# 2d_printer.net
KiCad netlist of a schematic drawn in EAGLE
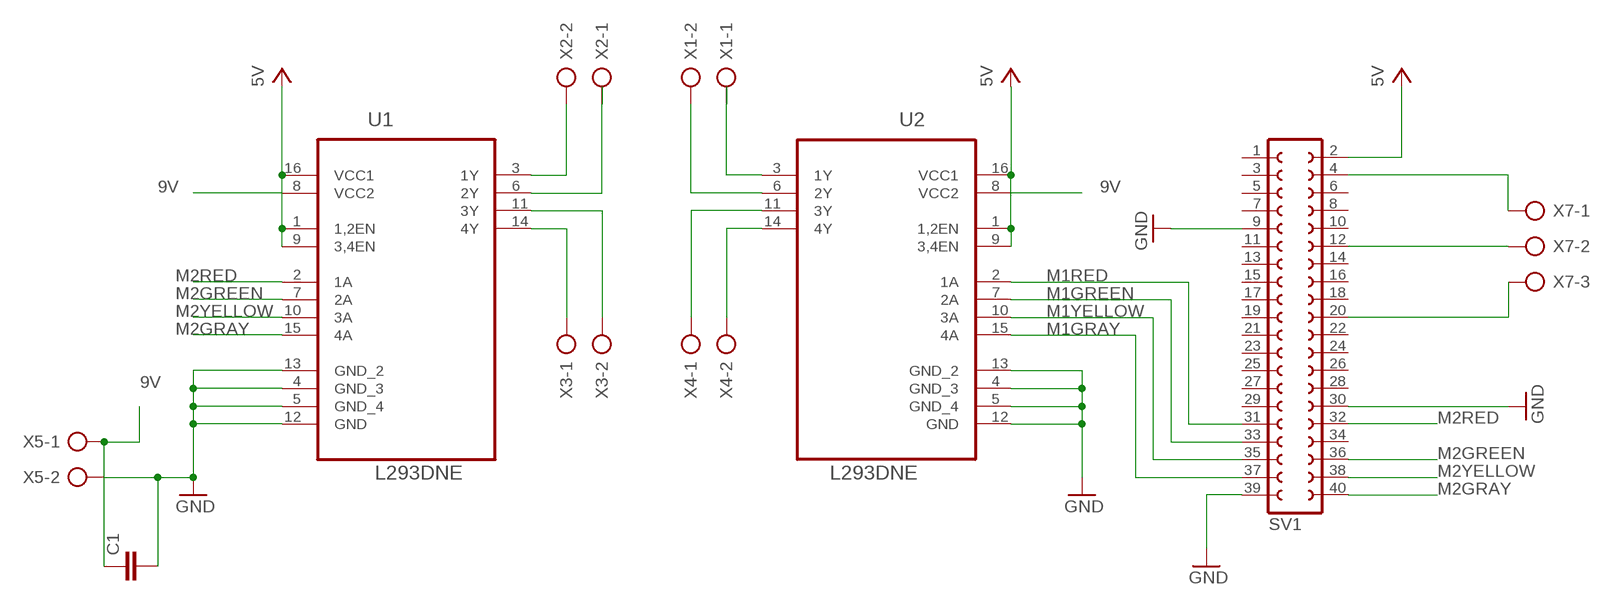
[diagram p0: schematic, sheet 1]

(export (version "E")
  (design (tool "Eeschema 10.0.6"))
  (components
    (comp (ref "C1")
      (value "C2.5/2")
      (footprint "eagle-import:C2.5-2")
      (libsource (lib "eagle-import") (part "C2.5/2"))
    )
    (comp (ref "SV1")
      (value "FE20-2")
      (footprint "eagle-import:FE20-2")
      (libsource (lib "eagle-import") (part "FE20-2"))
    )
    (comp (ref "U1")
      (value "L293DNE")
      (footprint "eagle-import:DIP254P762X508-16")
      (fields (field (name "MF") "Texas Instruments"))
      (libsource (lib "eagle-import") (part "L293DNE"))
    )
    (comp (ref "U2")
      (value "L293DNE")
      (footprint "eagle-import:DIP254P762X508-16")
      (fields (field (name "MF") "Texas Instruments"))
      (libsource (lib "eagle-import") (part "L293DNE"))
    )
    (comp (ref "X1")
      (value "AK300/2")
      (footprint "eagle-import:AK300_2")
      (libsource (lib "eagle-import") (part "AK300/2"))
    )
    (comp (ref "X2")
      (value "AK300/2")
      (footprint "eagle-import:AK300_2")
      (libsource (lib "eagle-import") (part "AK300/2"))
    )
    (comp (ref "X3")
      (value "AK300/2")
      (footprint "eagle-import:AK300_2")
      (libsource (lib "eagle-import") (part "AK300/2"))
    )
    (comp (ref "X4")
      (value "AK300/2")
      (footprint "eagle-import:AK300_2")
      (libsource (lib "eagle-import") (part "AK300/2"))
    )
    (comp (ref "X5")
      (value "AK300/2")
      (footprint "eagle-import:AK300_2")
      (libsource (lib "eagle-import") (part "AK300/2"))
    )
    (comp (ref "X7")
      (value "AK300/3")
      (footprint "eagle-import:AK300_3")
      (libsource (lib "eagle-import") (part "AK300/3"))
    )
  )
  (nets
    (net (code "1") (name "/9V") (class "Default")
      (node (ref "C1") (pin "1") (pinfunction "1_1") (pintype "passive"))
      (node (ref "U1") (pin "8") (pinfunction "VCC2_8") (pintype "power_in"))
      (node (ref "U2") (pin "8") (pinfunction "VCC2_8") (pintype "power_in"))
      (node (ref "X5") (pin "1") (pinfunction "KL_1") (pintype "passive"))
    )
    (net (code "2") (name "/M1GRAY") (class "Default")
      (node (ref "SV1") (pin "37") (pinfunction "37_37") (pintype "passive"))
      (node (ref "U2") (pin "15") (pinfunction "4A_15") (pintype "input"))
    )
    (net (code "3") (name "/M1GREEN") (class "Default")
      (node (ref "SV1") (pin "33") (pinfunction "33_33") (pintype "passive"))
      (node (ref "U2") (pin "7") (pinfunction "2A_7") (pintype "input"))
    )
    (net (code "4") (name "/M1RED") (class "Default")
      (node (ref "SV1") (pin "31") (pinfunction "31_31") (pintype "passive"))
      (node (ref "U2") (pin "2") (pinfunction "1A_2") (pintype "input"))
    )
    (net (code "5") (name "/M1YELLOW") (class "Default")
      (node (ref "SV1") (pin "35") (pinfunction "35_35") (pintype "passive"))
      (node (ref "U2") (pin "10") (pinfunction "3A_10") (pintype "input"))
    )
    (net (code "6") (name "/M2GRAY") (class "Default")
      (node (ref "SV1") (pin "40") (pinfunction "40_40") (pintype "passive"))
      (node (ref "U1") (pin "15") (pinfunction "4A_15") (pintype "input"))
    )
    (net (code "7") (name "/M2GREEN") (class "Default")
      (node (ref "SV1") (pin "36") (pinfunction "36_36") (pintype "passive"))
      (node (ref "U1") (pin "7") (pinfunction "2A_7") (pintype "input"))
    )
    (net (code "8") (name "/M2RED") (class "Default")
      (node (ref "SV1") (pin "32") (pinfunction "32_32") (pintype "passive"))
      (node (ref "U1") (pin "2") (pinfunction "1A_2") (pintype "input"))
    )
    (net (code "9") (name "/M2YELLOW") (class "Default")
      (node (ref "SV1") (pin "38") (pinfunction "38_38") (pintype "passive"))
      (node (ref "U1") (pin "10") (pinfunction "3A_10") (pintype "input"))
    )
    (net (code "10") (name "5V") (class "Default")
      (node (ref "SV1") (pin "2") (pinfunction "2_2") (pintype "passive"))
      (node (ref "U1") (pin "1") (pinfunction "1,2EN_1") (pintype "input"))
      (node (ref "U1") (pin "16") (pinfunction "VCC1_16") (pintype "power_in"))
      (node (ref "U1") (pin "9") (pinfunction "3,4EN_9") (pintype "input"))
      (node (ref "U2") (pin "1") (pinfunction "1,2EN_1") (pintype "input"))
      (node (ref "U2") (pin "16") (pinfunction "VCC1_16") (pintype "power_in"))
      (node (ref "U2") (pin "9") (pinfunction "3,4EN_9") (pintype "input"))
    )
    (net (code "11") (name "GND") (class "Default")
      (node (ref "C1") (pin "2") (pinfunction "2_2") (pintype "passive"))
      (node (ref "SV1") (pin "30") (pinfunction "30_30") (pintype "passive"))
      (node (ref "SV1") (pin "39") (pinfunction "39_39") (pintype "passive"))
      (node (ref "SV1") (pin "9") (pinfunction "9_9") (pintype "passive"))
      (node (ref "U1") (pin "12") (pinfunction "GND_12") (pintype "passive"))
      (node (ref "U1") (pin "13") (pinfunction "GND_2_13") (pintype "passive"))
      (node (ref "U1") (pin "4") (pinfunction "GND_3_4") (pintype "passive"))
      (node (ref "U1") (pin "5") (pinfunction "GND_4_5") (pintype "passive"))
      (node (ref "U2") (pin "12") (pinfunction "GND_12") (pintype "passive"))
      (node (ref "U2") (pin "13") (pinfunction "GND_2_13") (pintype "passive"))
      (node (ref "U2") (pin "4") (pinfunction "GND_3_4") (pintype "passive"))
      (node (ref "U2") (pin "5") (pinfunction "GND_4_5") (pintype "passive"))
      (node (ref "X5") (pin "2") (pinfunction "KL_2") (pintype "passive"))
    )
    (net (code "12") (name "Net-(U1-1Y)") (class "Default")
      (node (ref "U1") (pin "3") (pinfunction "1Y_3") (pintype "output"))
      (node (ref "X2") (pin "2") (pinfunction "KL_2") (pintype "passive"))
    )
    (net (code "13") (name "Net-(U1-2Y)") (class "Default")
      (node (ref "U1") (pin "6") (pinfunction "2Y_6") (pintype "output"))
      (node (ref "X2") (pin "1") (pinfunction "KL_1") (pintype "passive"))
    )
    (net (code "14") (name "Net-(U1-3Y)") (class "Default")
      (node (ref "U1") (pin "11") (pinfunction "3Y_11") (pintype "output"))
      (node (ref "X3") (pin "2") (pinfunction "KL_2") (pintype "passive"))
    )
    (net (code "15") (name "Net-(U1-4Y)") (class "Default")
      (node (ref "U1") (pin "14") (pinfunction "4Y_14") (pintype "output"))
      (node (ref "X3") (pin "1") (pinfunction "KL_1") (pintype "passive"))
    )
    (net (code "16") (name "Net-(U2-1Y)") (class "Default")
      (node (ref "U2") (pin "3") (pinfunction "1Y_3") (pintype "output"))
      (node (ref "X1") (pin "1") (pinfunction "KL_1") (pintype "passive"))
    )
    (net (code "17") (name "Net-(U2-2Y)") (class "Default")
      (node (ref "U2") (pin "6") (pinfunction "2Y_6") (pintype "output"))
      (node (ref "X1") (pin "2") (pinfunction "KL_2") (pintype "passive"))
    )
    (net (code "18") (name "Net-(U2-3Y)") (class "Default")
      (node (ref "U2") (pin "11") (pinfunction "3Y_11") (pintype "output"))
      (node (ref "X4") (pin "1") (pinfunction "KL_1") (pintype "passive"))
    )
    (net (code "19") (name "Net-(U2-4Y)") (class "Default")
      (node (ref "U2") (pin "14") (pinfunction "4Y_14") (pintype "output"))
      (node (ref "X4") (pin "2") (pinfunction "KL_2") (pintype "passive"))
    )
    (net (code "20") (name "Net-(X7A-KL)") (class "Default")
      (node (ref "SV1") (pin "4") (pinfunction "4_4") (pintype "passive"))
      (node (ref "X7") (pin "1") (pinfunction "KL_1") (pintype "passive"))
    )
    (net (code "21") (name "Net-(X7B-KL)") (class "Default")
      (node (ref "SV1") (pin "12") (pinfunction "12_12") (pintype "passive"))
      (node (ref "X7") (pin "2") (pinfunction "KL_2") (pintype "passive"))
    )
    (net (code "22") (name "Net-(X7C-KL)") (class "Default")
      (node (ref "SV1") (pin "20") (pinfunction "20_20") (pintype "passive"))
      (node (ref "X7") (pin "3") (pinfunction "KL_3") (pintype "passive"))
    )
    (net (code "23") (name "unconnected-(SV1-Pad1)") (class "Default")
      (node (ref "SV1") (pin "1") (pinfunction "1_1") (pintype "passive"))
    )
    (net (code "24") (name "unconnected-(SV1-Pad3)") (class "Default")
      (node (ref "SV1") (pin "3") (pinfunction "3_3") (pintype "passive"))
    )
    (net (code "25") (name "unconnected-(SV1-Pad5)") (class "Default")
      (node (ref "SV1") (pin "5") (pinfunction "5_5") (pintype "passive"))
    )
    (net (code "26") (name "unconnected-(SV1-Pad6)") (class "Default")
      (node (ref "SV1") (pin "6") (pinfunction "6_6") (pintype "passive"))
    )
    (net (code "27") (name "unconnected-(SV1-Pad7)") (class "Default")
      (node (ref "SV1") (pin "7") (pinfunction "7_7") (pintype "passive"))
    )
    (net (code "28") (name "unconnected-(SV1-Pad8)") (class "Default")
      (node (ref "SV1") (pin "8") (pinfunction "8_8") (pintype "passive"))
    )
    (net (code "29") (name "unconnected-(SV1-Pad10)") (class "Default")
      (node (ref "SV1") (pin "10") (pinfunction "10_10") (pintype "passive"))
    )
    (net (code "30") (name "unconnected-(SV1-Pad11)") (class "Default")
      (node (ref "SV1") (pin "11") (pinfunction "11_11") (pintype "passive"))
    )
    (net (code "31") (name "unconnected-(SV1-Pad13)") (class "Default")
      (node (ref "SV1") (pin "13") (pinfunction "13_13") (pintype "passive"))
    )
    (net (code "32") (name "unconnected-(SV1-Pad14)") (class "Default")
      (node (ref "SV1") (pin "14") (pinfunction "14_14") (pintype "passive"))
    )
    (net (code "33") (name "unconnected-(SV1-Pad15)") (class "Default")
      (node (ref "SV1") (pin "15") (pinfunction "15_15") (pintype "passive"))
    )
    (net (code "34") (name "unconnected-(SV1-Pad16)") (class "Default")
      (node (ref "SV1") (pin "16") (pinfunction "16_16") (pintype "passive"))
    )
    (net (code "35") (name "unconnected-(SV1-Pad17)") (class "Default")
      (node (ref "SV1") (pin "17") (pinfunction "17_17") (pintype "passive"))
    )
    (net (code "36") (name "unconnected-(SV1-Pad18)") (class "Default")
      (node (ref "SV1") (pin "18") (pinfunction "18_18") (pintype "passive"))
    )
    (net (code "37") (name "unconnected-(SV1-Pad19)") (class "Default")
      (node (ref "SV1") (pin "19") (pinfunction "19_19") (pintype "passive"))
    )
    (net (code "38") (name "unconnected-(SV1-Pad21)") (class "Default")
      (node (ref "SV1") (pin "21") (pinfunction "21_21") (pintype "passive"))
    )
    (net (code "39") (name "unconnected-(SV1-Pad22)") (class "Default")
      (node (ref "SV1") (pin "22") (pinfunction "22_22") (pintype "passive"))
    )
    (net (code "40") (name "unconnected-(SV1-Pad23)") (class "Default")
      (node (ref "SV1") (pin "23") (pinfunction "23_23") (pintype "passive"))
    )
    (net (code "41") (name "unconnected-(SV1-Pad24)") (class "Default")
      (node (ref "SV1") (pin "24") (pinfunction "24_24") (pintype "passive"))
    )
    (net (code "42") (name "unconnected-(SV1-Pad25)") (class "Default")
      (node (ref "SV1") (pin "25") (pinfunction "25_25") (pintype "passive"))
    )
    (net (code "43") (name "unconnected-(SV1-Pad26)") (class "Default")
      (node (ref "SV1") (pin "26") (pinfunction "26_26") (pintype "passive"))
    )
    (net (code "44") (name "unconnected-(SV1-Pad27)") (class "Default")
      (node (ref "SV1") (pin "27") (pinfunction "27_27") (pintype "passive"))
    )
    (net (code "45") (name "unconnected-(SV1-Pad28)") (class "Default")
      (node (ref "SV1") (pin "28") (pinfunction "28_28") (pintype "passive"))
    )
    (net (code "46") (name "unconnected-(SV1-Pad29)") (class "Default")
      (node (ref "SV1") (pin "29") (pinfunction "29_29") (pintype "passive"))
    )
    (net (code "47") (name "unconnected-(SV1-Pad34)") (class "Default")
      (node (ref "SV1") (pin "34") (pinfunction "34_34") (pintype "passive"))
    )
  )
)
